# main_gyro_acc_only.net
KiCad netlist of a schematic drawn in Altium Designer
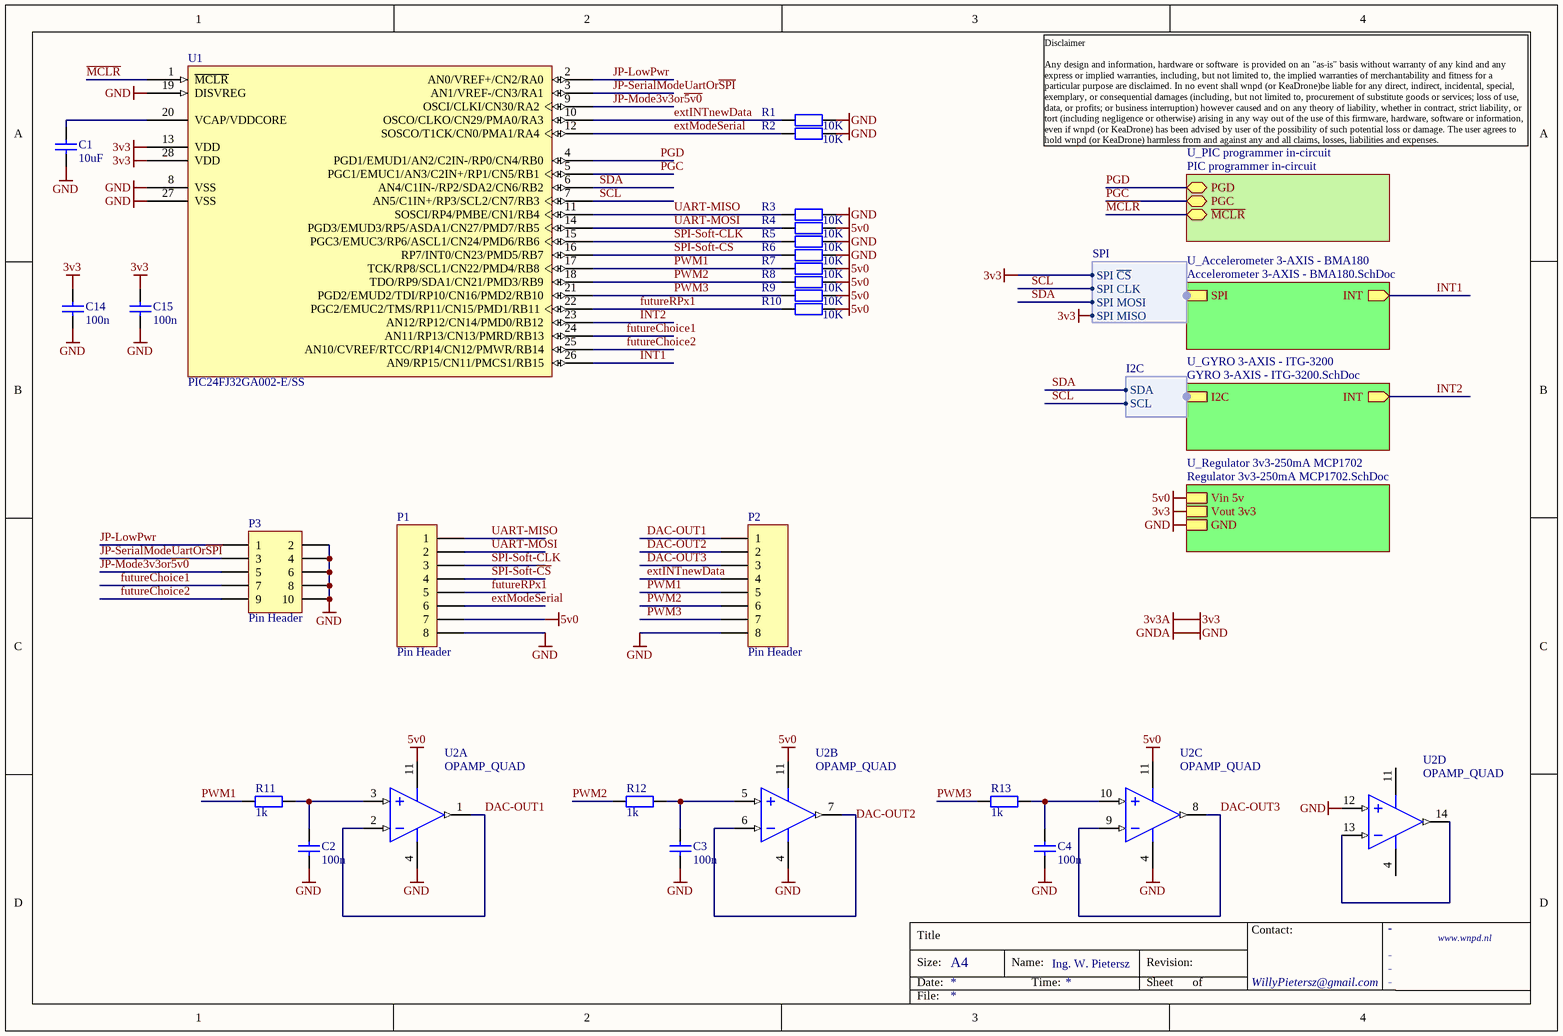
[diagram p0: main_gyro+acc only.SchDoc]

(export (version "E")
  (design (tool "Eeschema 10.0.6"))
  (components
    (comp (ref "C1")
      (value "10uF")
      (footprint "C1206")
      (fields
        (field (name "VOLTAGE") "10V")
        (field (name "TOLERANCE") "0.1")
        (field (name "AUTHOR") "Willem Pietersz")
      )
      (libsource (lib "OurDb") (part "cap_NonPolar"))
    )
    (comp (ref "C2")
      (value "100n")
      (footprint "C0805")
      (fields (field (name "TOLERANCE") "0.1") (field (name "AUTHOR") "Willy Pietersz"))
      (libsource (lib "OurDb") (part "cap_NonPolar"))
    )
    (comp (ref "C3")
      (value "100n")
      (footprint "C0805")
      (fields (field (name "TOLERANCE") "0.1") (field (name "AUTHOR") "Willy Pietersz"))
      (libsource (lib "OurDb") (part "cap_NonPolar"))
    )
    (comp (ref "C4")
      (value "100n")
      (footprint "C0805")
      (fields (field (name "TOLERANCE") "0.1") (field (name "AUTHOR") "Willy Pietersz"))
      (libsource (lib "OurDb") (part "cap_NonPolar"))
    )
    (comp (ref "C14")
      (value "100n")
      (footprint "C0805")
      (fields (field (name "TOLERANCE") "0.1") (field (name "AUTHOR") "Willy Pietersz"))
      (libsource (lib "OurDb") (part "cap_NonPolar"))
    )
    (comp (ref "C15")
      (value "100n")
      (footprint "C0805")
      (fields (field (name "TOLERANCE") "0.1") (field (name "AUTHOR") "Willy Pietersz"))
      (libsource (lib "OurDb") (part "cap_NonPolar"))
    )
    (comp (ref "P1")
      (value "Pin Header")
      (footprint "PH1x8_2.54")
      (description "Con1x8")
      (fields (field (name "PART NUMBER") "PH1x8") (field (name "AUTHOR") "Willy Pietersz"))
      (libsource (lib "OurDb") (part "Con1x8"))
    )
    (comp (ref "P2")
      (value "Pin Header")
      (footprint "PH1x8_2.54")
      (description "Con1x8")
      (fields (field (name "PART NUMBER") "PH1x8") (field (name "AUTHOR") "Willy Pietersz"))
      (libsource (lib "") (part "Con1x8_1"))
    )
    (comp (ref "P3")
      (value "Pin Header")
      (footprint "PH2x5_2.54")
      (description "Header, 5-Pin, Dual row")
      (fields (field (name "PART NUMBER") "PH2x5") (field (name "AUTHOR") "Willy Pietersz"))
      (libsource (lib "OurDb") (part "Con2x5"))
    )
    (comp (ref "R1")
      (value "10K")
      (footprint "R0805")
      (description "Resistor")
      (fields
        (field (name "POWER") "0.25W")
        (field (name "TOLERANCE") "0.05")
        (field (name "PUBLISHER") "Altium Limited")
        (field (name "AUTHOR") "Willy Pietersz")
      )
      (libsource (lib "OurDb") (part "RESISTOR"))
    )
    (comp (ref "R2")
      (value "10K")
      (footprint "R0805")
      (description "Resistor")
      (fields
        (field (name "POWER") "0.25W")
        (field (name "TOLERANCE") "0.05")
        (field (name "PUBLISHER") "Altium Limited")
        (field (name "AUTHOR") "Willy Pietersz")
      )
      (libsource (lib "OurDb") (part "RESISTOR"))
    )
    (comp (ref "R3")
      (value "10K")
      (footprint "R0805")
      (description "Resistor")
      (fields
        (field (name "POWER") "0.25W")
        (field (name "TOLERANCE") "0.05")
        (field (name "PUBLISHER") "Altium Limited")
        (field (name "AUTHOR") "Willy Pietersz")
      )
      (libsource (lib "OurDb") (part "RESISTOR"))
    )
    (comp (ref "R4")
      (value "10K")
      (footprint "R0805")
      (description "Resistor")
      (fields
        (field (name "POWER") "0.25W")
        (field (name "TOLERANCE") "0.05")
        (field (name "PUBLISHER") "Altium Limited")
        (field (name "AUTHOR") "Willy Pietersz")
      )
      (libsource (lib "OurDb") (part "RESISTOR"))
    )
    (comp (ref "R5")
      (value "10K")
      (footprint "R0805")
      (description "Resistor")
      (fields
        (field (name "POWER") "0.25W")
        (field (name "TOLERANCE") "0.05")
        (field (name "PUBLISHER") "Altium Limited")
        (field (name "AUTHOR") "Willy Pietersz")
      )
      (libsource (lib "OurDb") (part "RESISTOR"))
    )
    (comp (ref "R6")
      (value "10K")
      (footprint "R0805")
      (description "Resistor")
      (fields
        (field (name "POWER") "0.25W")
        (field (name "TOLERANCE") "0.05")
        (field (name "PUBLISHER") "Altium Limited")
        (field (name "AUTHOR") "Willy Pietersz")
      )
      (libsource (lib "OurDb") (part "RESISTOR"))
    )
    (comp (ref "R7")
      (value "10K")
      (footprint "R0805")
      (description "Resistor")
      (fields
        (field (name "POWER") "0.25W")
        (field (name "TOLERANCE") "0.05")
        (field (name "PUBLISHER") "Altium Limited")
        (field (name "AUTHOR") "Willy Pietersz")
      )
      (libsource (lib "OurDb") (part "RESISTOR"))
    )
    (comp (ref "R8")
      (value "10K")
      (footprint "R0805")
      (description "Resistor")
      (fields
        (field (name "POWER") "0.25W")
        (field (name "TOLERANCE") "0.05")
        (field (name "PUBLISHER") "Altium Limited")
        (field (name "AUTHOR") "Willy Pietersz")
      )
      (libsource (lib "OurDb") (part "RESISTOR"))
    )
    (comp (ref "R9")
      (value "10K")
      (footprint "R0805")
      (description "Resistor")
      (fields
        (field (name "POWER") "0.25W")
        (field (name "TOLERANCE") "0.05")
        (field (name "PUBLISHER") "Altium Limited")
        (field (name "AUTHOR") "Willy Pietersz")
      )
      (libsource (lib "OurDb") (part "RESISTOR"))
    )
    (comp (ref "R10")
      (value "10K")
      (footprint "R0805")
      (description "Resistor")
      (fields
        (field (name "POWER") "0.25W")
        (field (name "TOLERANCE") "0.05")
        (field (name "PUBLISHER") "Altium Limited")
        (field (name "AUTHOR") "Willy Pietersz")
      )
      (libsource (lib "OurDb") (part "RESISTOR"))
    )
    (comp (ref "R11")
      (value "1k")
      (footprint "R0805")
      (description "Resistor")
      (fields
        (field (name "PART NUMBER") "1K")
        (field (name "POWER") "0.25W")
        (field (name "PUBLISHER") "Altium Limited")
        (field (name "AUTHOR") "Willy Pietersz")
      )
      (libsource (lib "OurDb") (part "RESISTOR"))
    )
    (comp (ref "R12")
      (value "1k")
      (footprint "R0805")
      (description "Resistor")
      (fields
        (field (name "PART NUMBER") "1K")
        (field (name "POWER") "0.25W")
        (field (name "PUBLISHER") "Altium Limited")
        (field (name "AUTHOR") "Willy Pietersz")
      )
      (libsource (lib "OurDb") (part "RESISTOR"))
    )
    (comp (ref "R13")
      (value "1k")
      (footprint "R0805")
      (description "Resistor")
      (fields
        (field (name "PART NUMBER") "1K")
        (field (name "POWER") "0.25W")
        (field (name "PUBLISHER") "Altium Limited")
        (field (name "AUTHOR") "Willy Pietersz")
      )
      (libsource (lib "OurDb") (part "RESISTOR"))
    )
    (comp (ref "U1")
      (value "PIC24FJ32GA002-E/SS")
      (footprint "SSOP-SS28_N")
      (fields (field (name "PUBLISHER") "Altium Limited"))
      (libsource (lib "Microchip Microcontroller 16-Bit PIC24F") (part "PIC24FJ32GA002-E/SS"))
    )
    (comp (ref "U2")
      (value "OPAMP_QUAD")
      (footprint "SOIC-14")
      (description "OpAmp")
      (fields (field (name "PART NUMBER") "MCP6244-E/SN") (field (name "AUTHOR") "Willem Pietersz"))
      (libsource (lib "OurDb") (part "OPAMP_QUAD"))
    )
  )
  (nets
    (net (code "1") (name "/DAC-OUT1") (class "Default")
      (node (ref "P2") (pin "1") (pinfunction "1_1") (pintype "passive"))
      (node (ref "U2") (pin "1") (pinfunction "VOUTA_1") (pintype "output"))
      (node (ref "U2") (pin "2") (pinfunction "VINA-_2") (pintype "input"))
    )
    (net (code "2") (name "/DAC-OUT2") (class "Default")
      (node (ref "P2") (pin "2") (pinfunction "2_2") (pintype "passive"))
      (node (ref "U2") (pin "6") (pinfunction "VINB-_6") (pintype "input"))
      (node (ref "U2") (pin "7") (pinfunction "VOUTB_7") (pintype "output"))
    )
    (net (code "3") (name "/DAC-OUT3") (class "Default")
      (node (ref "P2") (pin "3") (pinfunction "3_3") (pintype "passive"))
      (node (ref "U2") (pin "8") (pinfunction "VOUTC_8") (pintype "output"))
      (node (ref "U2") (pin "9") (pinfunction "VINC-_9") (pintype "input"))
    )
    (net (code "5") (name "/INT1") (class "Default")
      (node (ref "U1") (pin "26") (pinfunction "AN9/RP15/CN11/PMCS1/RB15_26") (pintype "bidirectional"))
    )
    (net (code "6") (name "/INT2") (class "Default")
      (node (ref "U1") (pin "23") (pinfunction "AN12/RP12/CN14/PMD0/RB12_23") (pintype "bidirectional"))
    )
    (net (code "7") (name "/JP-LowPwr") (class "Default")
      (node (ref "P3") (pin "1") (pinfunction "1_1") (pintype "passive"))
      (node (ref "U1") (pin "2") (pinfunction "AN0/VREF+/CN2/RA0_2") (pintype "bidirectional"))
    )
    (net (code "8") (name "/JP-Mode3v3or~{5v0}") (class "Default")
      (node (ref "P3") (pin "5") (pinfunction "5_5") (pintype "passive"))
      (node (ref "U1") (pin "9") (pinfunction "OSCI/CLKI/CN30/RA2_9") (pintype "bidirectional"))
    )
    (net (code "9") (name "/JP-SerialModeUartOr~{SPI}") (class "Default")
      (node (ref "P3") (pin "3") (pinfunction "3_3") (pintype "passive"))
      (node (ref "U1") (pin "3") (pinfunction "AN1/VREF-/CN3/RA1_3") (pintype "bidirectional"))
    )
    (net (code "10") (name "/PGC") (class "Default")
      (node (ref "U1") (pin "5") (pinfunction "PGC1/EMUC1/AN3/C2IN+/RP1/CN5/RB1_5") (pintype "bidirectional"))
    )
    (net (code "11") (name "/PGD") (class "Default")
      (node (ref "U1") (pin "4") (pinfunction "PGD1/EMUD1/AN2/C2IN-/RP0/CN4/RB0_4") (pintype "bidirectional"))
    )
    (net (code "12") (name "/PWM1") (class "Default")
      (node (ref "P2") (pin "5") (pinfunction "5_5") (pintype "passive"))
      (node (ref "R11") (pin "2") (pinfunction "2_2") (pintype "passive"))
      (node (ref "R7") (pin "2") (pinfunction "2_2") (pintype "passive"))
      (node (ref "U1") (pin "17") (pinfunction "TCK/RP8/SCL1/CN22/PMD4/RB8_17") (pintype "bidirectional"))
    )
    (net (code "13") (name "/PWM2") (class "Default")
      (node (ref "P2") (pin "6") (pinfunction "6_6") (pintype "passive"))
      (node (ref "R12") (pin "2") (pinfunction "2_2") (pintype "passive"))
      (node (ref "R8") (pin "2") (pinfunction "2_2") (pintype "passive"))
      (node (ref "U1") (pin "18") (pinfunction "TDO/RP9/SDA1/CN21/PMD3/RB9_18") (pintype "bidirectional"))
    )
    (net (code "14") (name "/PWM3") (class "Default")
      (node (ref "P2") (pin "7") (pinfunction "7_7") (pintype "passive"))
      (node (ref "R13") (pin "2") (pinfunction "2_2") (pintype "passive"))
      (node (ref "R9") (pin "2") (pinfunction "2_2") (pintype "passive"))
      (node (ref "U1") (pin "21") (pinfunction "PGD2/EMUD2/TDI/RP10/CN16/PMD2/RB10_21") (pintype "bidirectional"))
    )
    (net (code "15") (name "/SCL") (class "Default")
      (node (ref "U1") (pin "7") (pinfunction "AN5/C1IN+/RP3/SCL2/CN7/RB3_7") (pintype "bidirectional"))
    )
    (net (code "16") (name "/SDA") (class "Default")
      (node (ref "U1") (pin "6") (pinfunction "AN4/C1IN-/RP2/SDA2/CN6/RB2_6") (pintype "bidirectional"))
    )
    (net (code "17") (name "/SPI-Soft-CLK") (class "Default")
      (node (ref "P1") (pin "3") (pinfunction "3_3") (pintype "passive"))
      (node (ref "R5") (pin "2") (pinfunction "2_2") (pintype "passive"))
      (node (ref "U1") (pin "15") (pinfunction "PGC3/EMUC3/RP6/ASCL1/CN24/PMD6/RB6_15") (pintype "bidirectional"))
    )
    (net (code "18") (name "/SPI-Soft-~{CS}") (class "Default")
      (node (ref "P1") (pin "4") (pinfunction "4_4") (pintype "passive"))
      (node (ref "R6") (pin "2") (pinfunction "2_2") (pintype "passive"))
      (node (ref "U1") (pin "16") (pinfunction "RP7/INT0/CN23/PMD5/RB7_16") (pintype "bidirectional"))
    )
    (net (code "20") (name "/UART-MISO") (class "Default")
      (node (ref "P1") (pin "1") (pinfunction "1_1") (pintype "passive"))
      (node (ref "R3") (pin "2") (pinfunction "2_2") (pintype "passive"))
      (node (ref "U1") (pin "11") (pinfunction "SOSCI/RP4/PMBE/CN1/RB4_11") (pintype "bidirectional"))
    )
    (net (code "21") (name "/UART-MOSI") (class "Default")
      (node (ref "P1") (pin "2") (pinfunction "2_2") (pintype "passive"))
      (node (ref "R4") (pin "2") (pinfunction "2_2") (pintype "passive"))
      (node (ref "U1") (pin "14") (pinfunction "PGD3/EMUD3/RP5/ASDA1/CN27/PMD7/RB5_14") (pintype "bidirectional"))
    )
    (net (code "22") (name "/extINTnewData") (class "Default")
      (node (ref "P2") (pin "4") (pinfunction "4_4") (pintype "passive"))
      (node (ref "R1") (pin "2") (pinfunction "2_2") (pintype "passive"))
      (node (ref "U1") (pin "10") (pinfunction "OSCO/CLKO/CN29/PMA0/RA3_10") (pintype "bidirectional"))
    )
    (net (code "23") (name "/extModeSerial") (class "Default")
      (node (ref "P1") (pin "6") (pinfunction "6_6") (pintype "passive"))
      (node (ref "R2") (pin "2") (pinfunction "2_2") (pintype "passive"))
      (node (ref "U1") (pin "12") (pinfunction "SOSCO/T1CK/CN0/PMA1/RA4_12") (pintype "bidirectional"))
    )
    (net (code "24") (name "/futureChoice1") (class "Default")
      (node (ref "P3") (pin "7") (pinfunction "7_7") (pintype "passive"))
      (node (ref "U1") (pin "24") (pinfunction "AN11/RP13/CN13/PMRD/RB13_24") (pintype "bidirectional"))
    )
    (net (code "25") (name "/futureChoice2") (class "Default")
      (node (ref "P3") (pin "9") (pinfunction "9_9") (pintype "passive"))
      (node (ref "U1") (pin "25") (pinfunction "AN10/CVREF/RTCC/RP14/CN12/PMWR/RB14_25") (pintype "bidirectional"))
    )
    (net (code "26") (name "/futureRPx1") (class "Default")
      (node (ref "P1") (pin "5") (pinfunction "5_5") (pintype "passive"))
      (node (ref "R10") (pin "2") (pinfunction "2_2") (pintype "passive"))
      (node (ref "U1") (pin "22") (pinfunction "PGC2/EMUC2/TMS/RP11/CN15/PMD1/RB11_22") (pintype "bidirectional"))
    )
    (net (code "27") (name "/~{MCLR}") (class "Default")
      (node (ref "U1") (pin "1") (pinfunction "~{MCLR}_1") (pintype "input"))
    )
    (net (code "28") (name "3v3") (class "Default")
      (node (ref "C14") (pin "2") (pinfunction "2_2") (pintype "passive"))
      (node (ref "C15") (pin "2") (pinfunction "2_2") (pintype "passive"))
      (node (ref "U1") (pin "13") (pinfunction "VDD_13") (pintype "power_in"))
      (node (ref "U1") (pin "28") (pinfunction "VDD_28") (pintype "power_in"))
    )
    (net (code "29") (name "5v0") (class "Default")
      (node (ref "P1") (pin "7") (pinfunction "7_7") (pintype "passive"))
      (node (ref "R10") (pin "1") (pinfunction "1_1") (pintype "passive"))
      (node (ref "R4") (pin "1") (pinfunction "1_1") (pintype "passive"))
      (node (ref "R7") (pin "1") (pinfunction "1_1") (pintype "passive"))
      (node (ref "R8") (pin "1") (pinfunction "1_1") (pintype "passive"))
      (node (ref "R9") (pin "1") (pinfunction "1_1") (pintype "passive"))
      (node (ref "U2") (pin "11") (pinfunction "VSS_11") (pintype "power_in"))
    )
    (net (code "30") (name "GND") (class "Default")
      (node (ref "C1") (pin "1") (pinfunction "1_1") (pintype "passive"))
      (node (ref "C14") (pin "1") (pinfunction "1_1") (pintype "passive"))
      (node (ref "C15") (pin "1") (pinfunction "1_1") (pintype "passive"))
      (node (ref "C2") (pin "1") (pinfunction "1_1") (pintype "passive"))
      (node (ref "C3") (pin "1") (pinfunction "1_1") (pintype "passive"))
      (node (ref "C4") (pin "1") (pinfunction "1_1") (pintype "passive"))
      (node (ref "P1") (pin "8") (pinfunction "8_8") (pintype "passive"))
      (node (ref "P2") (pin "8") (pinfunction "8_8") (pintype "passive"))
      (node (ref "P3") (pin "10") (pinfunction "10_10") (pintype "passive"))
      (node (ref "P3") (pin "2") (pinfunction "2_2") (pintype "passive"))
      (node (ref "P3") (pin "4") (pinfunction "4_4") (pintype "passive"))
      (node (ref "P3") (pin "6") (pinfunction "6_6") (pintype "passive"))
      (node (ref "P3") (pin "8") (pinfunction "8_8") (pintype "passive"))
      (node (ref "R1") (pin "1") (pinfunction "1_1") (pintype "passive"))
      (node (ref "R2") (pin "1") (pinfunction "1_1") (pintype "passive"))
      (node (ref "R3") (pin "1") (pinfunction "1_1") (pintype "passive"))
      (node (ref "R5") (pin "1") (pinfunction "1_1") (pintype "passive"))
      (node (ref "R6") (pin "1") (pinfunction "1_1") (pintype "passive"))
      (node (ref "U1") (pin "19") (pinfunction "DISVREG_19") (pintype "input"))
      (node (ref "U1") (pin "27") (pinfunction "VSS_27") (pintype "power_in"))
      (node (ref "U1") (pin "8") (pinfunction "VSS_8") (pintype "power_in"))
      (node (ref "U2") (pin "12") (pinfunction "VIND+_12") (pintype "input"))
      (node (ref "U2") (pin "4") (pinfunction "VDD_4") (pintype "power_in"))
    )
    (net (code "31") (name "Net-(U1-VCAP{slash}VDDCORE)") (class "Default")
      (node (ref "C1") (pin "2") (pinfunction "2_2") (pintype "passive"))
      (node (ref "U1") (pin "20") (pinfunction "VCAP/VDDCORE_20") (pintype "power_in"))
    )
    (net (code "32") (name "Net-(U2A-VINA+)") (class "Default")
      (node (ref "C2") (pin "2") (pinfunction "2_2") (pintype "passive"))
      (node (ref "R11") (pin "1") (pinfunction "1_1") (pintype "passive"))
      (node (ref "U2") (pin "3") (pinfunction "VINA+_3") (pintype "input"))
    )
    (net (code "33") (name "Net-(U2B-VINB+)") (class "Default")
      (node (ref "C3") (pin "2") (pinfunction "2_2") (pintype "passive"))
      (node (ref "R12") (pin "1") (pinfunction "1_1") (pintype "passive"))
      (node (ref "U2") (pin "5") (pinfunction "VINB+_5") (pintype "input"))
    )
    (net (code "34") (name "Net-(U2C-VINC+)") (class "Default")
      (node (ref "C4") (pin "2") (pinfunction "2_2") (pintype "passive"))
      (node (ref "R13") (pin "1") (pinfunction "1_1") (pintype "passive"))
      (node (ref "U2") (pin "10") (pinfunction "VINC+_10") (pintype "input"))
    )
    (net (code "35") (name "Net-(U2D-VIND-)") (class "Default")
      (node (ref "U2") (pin "13") (pinfunction "VIND-_13") (pintype "input"))
      (node (ref "U2") (pin "14") (pinfunction "VOUTD_14") (pintype "output"))
    )
    (net (code "36") (name "unconnected-(U2D-VDD-Pad4)") (class "Default")
      (node (ref "U2") (pin "4") (pinfunction "VDD_4") (pintype "power_in"))
    )
    (net (code "37") (name "unconnected-(U2D-VSS-Pad11)") (class "Default")
      (node (ref "U2") (pin "11") (pinfunction "VSS_11") (pintype "power_in"))
    )
  )
)
